# 2-Charge_Discharge.net
KiCad netlist of a schematic drawn in Altium Designer
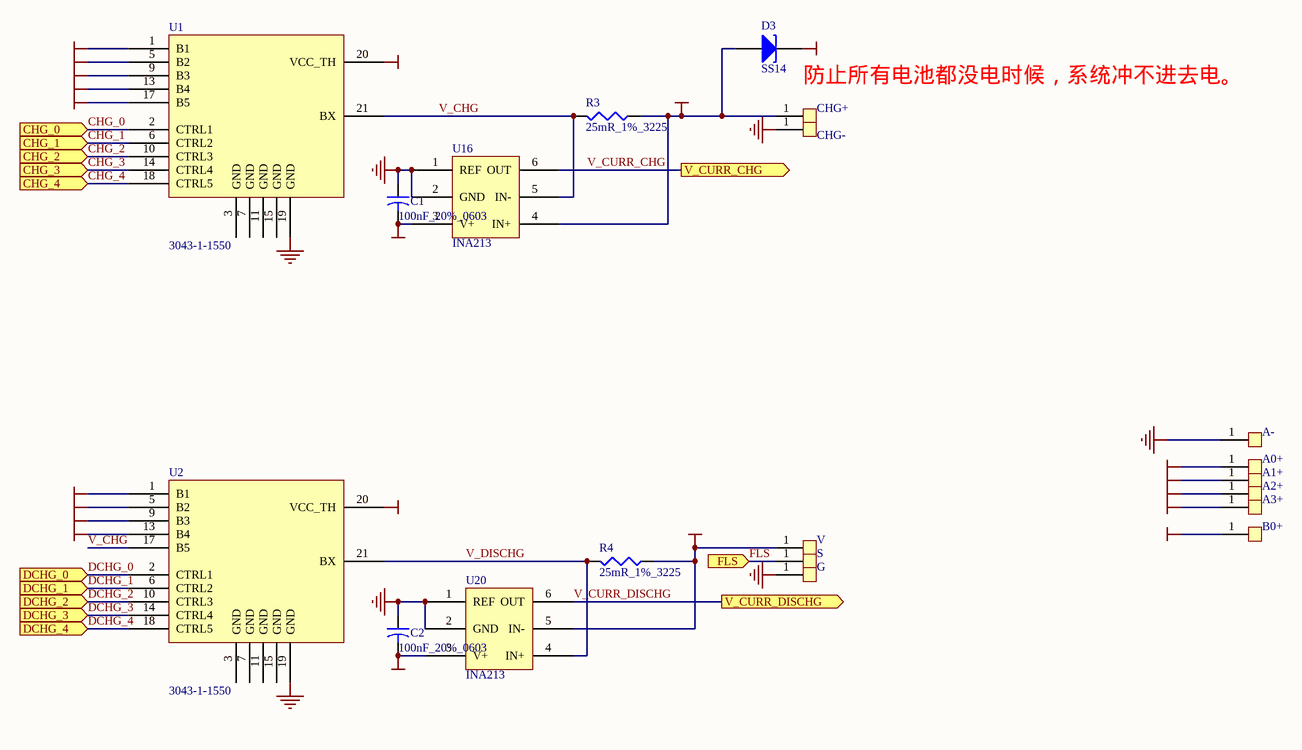
[diagram p0: 2-Charge&Discharge.SchDoc]

(export (version "E")
  (design (tool "Eeschema 10.0.6"))
  (components
    (comp (ref "A-") (value "ND") (footprint "END_1.5_2.8") (libsource (lib "Device") (part "ND")))
    (comp (ref "A0+") (value "ND") (footprint "END_1.5_2.8") (libsource (lib "Device") (part "ND")))
    (comp (ref "A1+") (value "ND") (footprint "END_1.5_2.8") (libsource (lib "Device") (part "ND")))
    (comp (ref "A2+") (value "ND") (footprint "END_1.5_2.8") (libsource (lib "Device") (part "ND")))
    (comp (ref "A3+") (value "ND") (footprint "END_1.5_2.8") (libsource (lib "Device") (part "ND")))
    (comp (ref "B0+") (value "ND") (footprint "END_1.5_2.8") (libsource (lib "Device") (part "ND")))
    (comp (ref "C1")
      (value "100nF_20%_0603")
      (footprint "C1608-0603")
      (description "Capacitor")
      (fields (field (name "PUBLISHER") "Altium Limited"))
      (libsource (lib "Miscellaneous Devices") (part "Cap2"))
    )
    (comp (ref "C2")
      (value "100nF_20%_0603")
      (footprint "C1608-0603")
      (description "Capacitor")
      (fields (field (name "PUBLISHER") "Altium Limited"))
      (libsource (lib "Miscellaneous Devices") (part "Cap2"))
    )
    (comp (ref "CHG+") (value "ND") (footprint "END_1.5_2.8") (libsource (lib "Device") (part "ND")))
    (comp (ref "CHG-") (value "ND") (footprint "END_1.5_2.8") (libsource (lib "Device") (part "ND")))
    (comp (ref "D3")
      (value "SS14")
      (footprint "DO-214AB_SS14")
      (description "Tunnel Diode - RLC Model")
      (fields (field (name "PUBLISHER") "Altium Limited"))
      (libsource (lib "Miscellaneous Devices") (part "D Tunnel1"))
    )
    (comp (ref "G") (value "ND") (footprint "END_1.5_2.8") (libsource (lib "Device") (part "ND")))
    (comp (ref "R3")
      (value "25mR_1%_3225")
      (footprint "CR6332-2512")
      (description "Resistor")
      (fields (field (name "PUBLISHER") "Altium Limited"))
      (libsource (lib "Miscellaneous Devices") (part "Res3"))
    )
    (comp (ref "R4")
      (value "25mR_1%_3225")
      (footprint "CR6332-2512")
      (description "Resistor")
      (fields (field (name "PUBLISHER") "Altium Limited"))
      (libsource (lib "Miscellaneous Devices") (part "Res3"))
    )
    (comp (ref "S") (value "ND") (footprint "END_1.5_2.8") (libsource (lib "Device") (part "ND")))
    (comp (ref "U1")
      (value "3043-1-1550")
      (footprint "3043-1-1550_V1.10")
      (libsource (lib "Device") (part "3043-1-1550"))
    )
    (comp (ref "U2")
      (value "3043-1-1550")
      (footprint "3043-1-1550_V1.10")
      (libsource (lib "Device") (part "3043-1-1550"))
    )
    (comp (ref "U16") (value "INA213") (footprint "SC70-6") (libsource (lib "Device") (part "INA213")))
    (comp (ref "U20") (value "INA213") (footprint "SC70-6") (libsource (lib "Device") (part "INA213")))
    (comp (ref "V") (value "ND") (footprint "END_1.5_2.8") (libsource (lib "Device") (part "ND")))
  )
  (nets
    (net (code "1") (name "/CHG_0") (class "Default")
      (node (ref "U1") (pin "2") (pinfunction "CTRL1_2") (pintype "passive"))
    )
    (net (code "2") (name "/CHG_1") (class "Default")
      (node (ref "U1") (pin "6") (pinfunction "CTRL2_6") (pintype "passive"))
    )
    (net (code "3") (name "/CHG_2") (class "Default")
      (node (ref "U1") (pin "10") (pinfunction "CTRL3_10") (pintype "passive"))
    )
    (net (code "4") (name "/CHG_3") (class "Default")
      (node (ref "U1") (pin "14") (pinfunction "CTRL4_14") (pintype "passive"))
    )
    (net (code "5") (name "/CHG_4") (class "Default")
      (node (ref "U1") (pin "18") (pinfunction "CTRL5_18") (pintype "passive"))
    )
    (net (code "6") (name "/DCHG_0") (class "Default")
      (node (ref "U2") (pin "2") (pinfunction "CTRL1_2") (pintype "passive"))
    )
    (net (code "7") (name "/DCHG_1") (class "Default")
      (node (ref "U2") (pin "6") (pinfunction "CTRL2_6") (pintype "passive"))
    )
    (net (code "8") (name "/DCHG_2") (class "Default")
      (node (ref "U2") (pin "10") (pinfunction "CTRL3_10") (pintype "passive"))
    )
    (net (code "9") (name "/DCHG_3") (class "Default")
      (node (ref "U2") (pin "14") (pinfunction "CTRL4_14") (pintype "passive"))
    )
    (net (code "10") (name "/DCHG_4") (class "Default")
      (node (ref "U2") (pin "18") (pinfunction "CTRL5_18") (pintype "passive"))
    )
    (net (code "11") (name "/FLS") (class "Default")
      (node (ref "S") (pin "1") (pinfunction "SW_1") (pintype "passive"))
    )
    (net (code "12") (name "/V_CHG") (class "Default")
      (node (ref "R3") (pin "2") (pinfunction "2_2") (pintype "passive"))
      (node (ref "U1") (pin "21") (pinfunction "BX_21") (pintype "passive"))
      (node (ref "U16") (pin "5") (pinfunction "IN-_5") (pintype "passive"))
      (node (ref "U2") (pin "17") (pinfunction "B5_17") (pintype "passive"))
    )
    (net (code "13") (name "/V_CURR_CHG") (class "Default")
      (node (ref "U16") (pin "6") (pinfunction "OUT_6") (pintype "passive"))
    )
    (net (code "14") (name "/V_CURR_DISCHG") (class "Default")
      (node (ref "U20") (pin "6") (pinfunction "OUT_6") (pintype "passive"))
    )
    (net (code "15") (name "/V_DISCHG") (class "Default")
      (node (ref "R4") (pin "2") (pinfunction "2_2") (pintype "passive"))
      (node (ref "U2") (pin "21") (pinfunction "BX_21") (pintype "passive"))
      (node (ref "U20") (pin "4") (pinfunction "IN+_4") (pintype "passive"))
    )
    (net (code "16") (name "GND") (class "Default")
      (node (ref "A-") (pin "1") (pinfunction "SW_1") (pintype "passive"))
      (node (ref "C1") (pin "1") (pinfunction "1_1") (pintype "passive"))
      (node (ref "C2") (pin "1") (pinfunction "1_1") (pintype "passive"))
      (node (ref "CHG-") (pin "1") (pinfunction "SW_1") (pintype "passive"))
      (node (ref "G") (pin "1") (pinfunction "SW_1") (pintype "passive"))
      (node (ref "U1") (pin "19") (pinfunction "GND_19") (pintype "passive"))
      (node (ref "U16") (pin "1") (pinfunction "REF_1") (pintype "passive"))
      (node (ref "U16") (pin "2") (pinfunction "GND_2") (pintype "passive"))
      (node (ref "U2") (pin "19") (pinfunction "GND_19") (pintype "passive"))
      (node (ref "U20") (pin "1") (pinfunction "REF_1") (pintype "passive"))
      (node (ref "U20") (pin "2") (pinfunction "GND_2") (pintype "passive"))
    )
    (net (code "17") (name "VCC_2V8") (class "Default")
      (node (ref "C1") (pin "2") (pinfunction "2_2") (pintype "passive"))
      (node (ref "C2") (pin "2") (pinfunction "2_2") (pintype "passive"))
      (node (ref "U16") (pin "3") (pinfunction "V+_3") (pintype "passive"))
      (node (ref "U20") (pin "3") (pinfunction "V+_3") (pintype "passive"))
    )
    (net (code "18") (name "VCC_CHARGE") (class "Default")
      (node (ref "CHG+") (pin "1") (pinfunction "SW_1") (pintype "passive"))
      (node (ref "D3") (pin "1") (pinfunction "A_1") (pintype "passive"))
      (node (ref "R3") (pin "1") (pinfunction "1_1") (pintype "passive"))
      (node (ref "U16") (pin "4") (pinfunction "IN+_4") (pintype "passive"))
    )
    (net (code "19") (name "VCC_DIS") (class "Default")
      (node (ref "R4") (pin "1") (pinfunction "1_1") (pintype "passive"))
      (node (ref "U20") (pin "5") (pinfunction "IN-_5") (pintype "passive"))
      (node (ref "V") (pin "1") (pinfunction "SW_1") (pintype "passive"))
    )
    (net (code "20") (name "VCC_TH") (class "Default")
      (node (ref "U1") (pin "20") (pinfunction "VCC_TH_20") (pintype "passive"))
      (node (ref "U2") (pin "20") (pinfunction "VCC_TH_20") (pintype "passive"))
    )
    (net (code "21") (name "V_BAK") (class "Default")
      (node (ref "B0+") (pin "1") (pinfunction "SW_1") (pintype "passive"))
      (node (ref "D3") (pin "2") (pinfunction "K_2") (pintype "passive"))
      (node (ref "U1") (pin "17") (pinfunction "B5_17") (pintype "passive"))
    )
    (net (code "22") (name "V_BT0") (class "Default")
      (node (ref "A0+") (pin "1") (pinfunction "SW_1") (pintype "passive"))
      (node (ref "U1") (pin "1") (pinfunction "B1_1") (pintype "passive"))
      (node (ref "U2") (pin "1") (pinfunction "B1_1") (pintype "passive"))
    )
    (net (code "23") (name "V_BT1") (class "Default")
      (node (ref "A1+") (pin "1") (pinfunction "SW_1") (pintype "passive"))
      (node (ref "U1") (pin "5") (pinfunction "B2_5") (pintype "passive"))
      (node (ref "U2") (pin "5") (pinfunction "B2_5") (pintype "passive"))
    )
    (net (code "24") (name "V_BT2") (class "Default")
      (node (ref "A2+") (pin "1") (pinfunction "SW_1") (pintype "passive"))
      (node (ref "U1") (pin "9") (pinfunction "B3_9") (pintype "passive"))
      (node (ref "U2") (pin "9") (pinfunction "B3_9") (pintype "passive"))
    )
    (net (code "25") (name "V_BT3") (class "Default")
      (node (ref "A3+") (pin "1") (pinfunction "SW_1") (pintype "passive"))
      (node (ref "U1") (pin "13") (pinfunction "B4_13") (pintype "passive"))
      (node (ref "U2") (pin "13") (pinfunction "B4_13") (pintype "passive"))
    )
    (net (code "26") (name "unconnected-(U1-GND-Pad3)") (class "Default")
      (node (ref "U1") (pin "3") (pinfunction "GND_3") (pintype "passive"))
    )
    (net (code "27") (name "unconnected-(U1-GND-Pad7)") (class "Default")
      (node (ref "U1") (pin "7") (pinfunction "GND_7") (pintype "passive"))
    )
    (net (code "28") (name "unconnected-(U1-GND-Pad11)") (class "Default")
      (node (ref "U1") (pin "11") (pinfunction "GND_11") (pintype "passive"))
    )
    (net (code "29") (name "unconnected-(U1-GND-Pad15)") (class "Default")
      (node (ref "U1") (pin "15") (pinfunction "GND_15") (pintype "passive"))
    )
    (net (code "30") (name "unconnected-(U2-GND-Pad3)") (class "Default")
      (node (ref "U2") (pin "3") (pinfunction "GND_3") (pintype "passive"))
    )
    (net (code "31") (name "unconnected-(U2-GND-Pad7)") (class "Default")
      (node (ref "U2") (pin "7") (pinfunction "GND_7") (pintype "passive"))
    )
    (net (code "32") (name "unconnected-(U2-GND-Pad11)") (class "Default")
      (node (ref "U2") (pin "11") (pinfunction "GND_11") (pintype "passive"))
    )
    (net (code "33") (name "unconnected-(U2-GND-Pad15)") (class "Default")
      (node (ref "U2") (pin "15") (pinfunction "GND_15") (pintype "passive"))
    )
  )
)
